# ESP32.net
KiCad netlist of a schematic drawn in Altium Designer
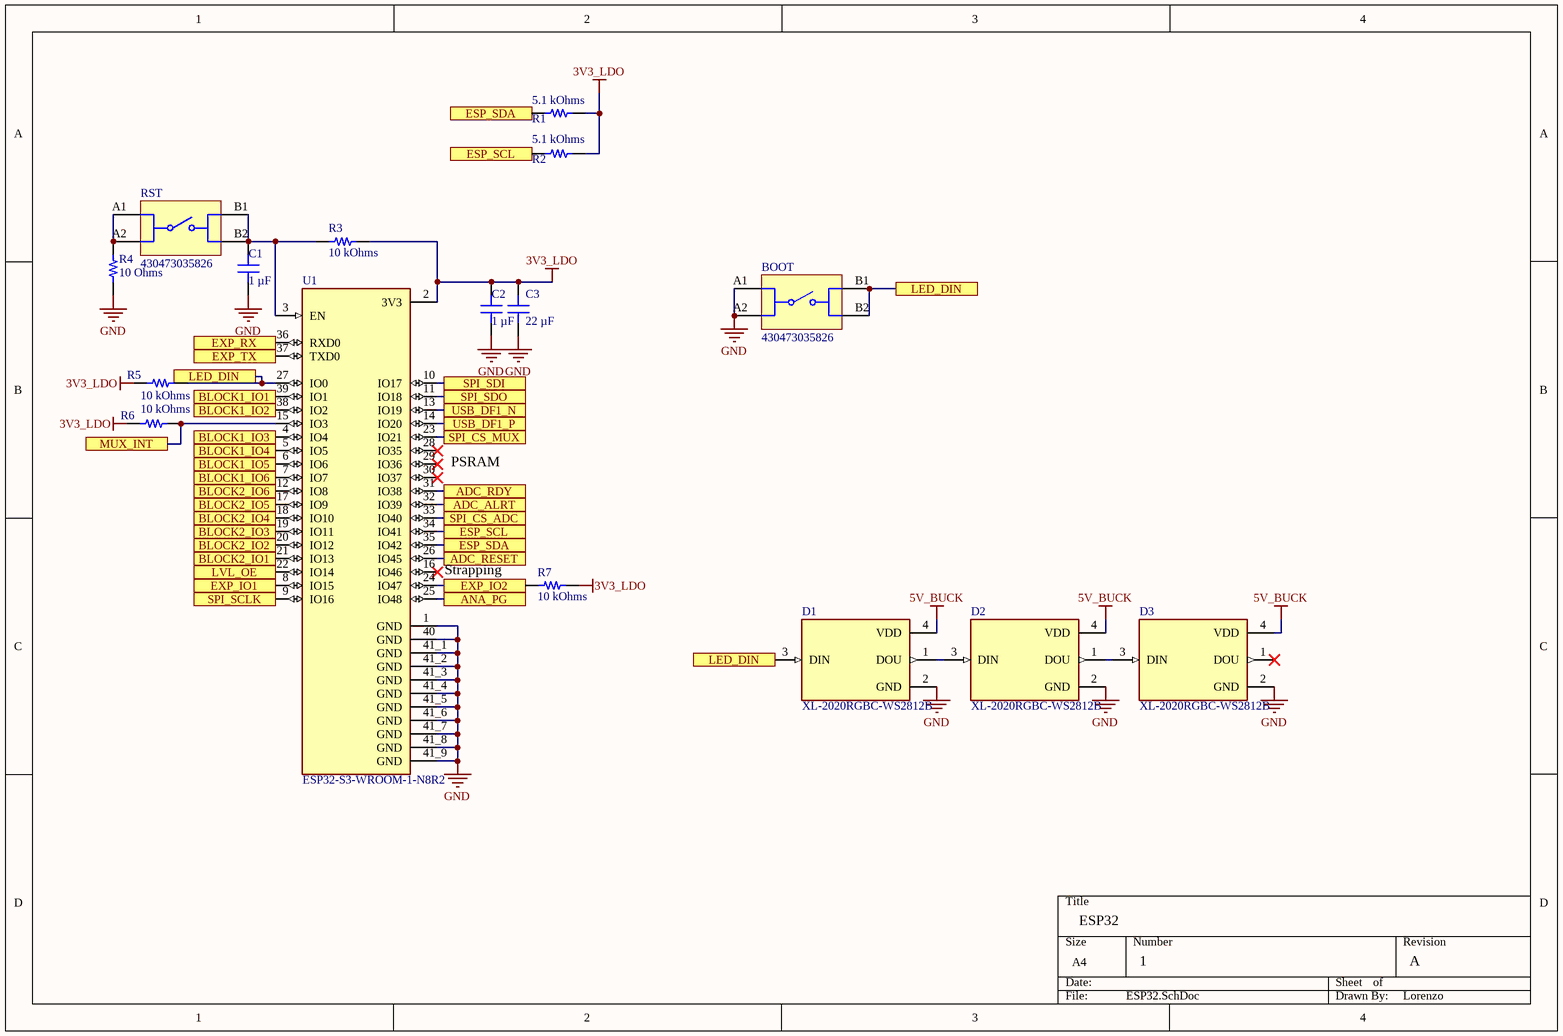
[diagram p0: ESP32.SchDoc]

(export (version "E")
  (design (tool "Eeschema 10.0.6"))
  (components
    (comp (ref "BOOT")
      (value "430473035826")
      (footprint "430473035826")
      (description "Switch Tactile Spst-no 0.05A 12V")
      (libsource (lib "Altium Content Vault") (part "SPST-NO_4P"))
    )
    (comp (ref "C1")
      (value "1 µF")
      (footprint "CAP 0603_1608")
      (description "CAP CER 1UF 50V X5R 0603")
      (fields
        (field (name "PART NUMBER") "C1608X5R1H105K080AB")
        (field (name "MANUFACTURER") "TDK Corporation")
      )
      (libsource (lib "Altium Database Library V2 Local") (part "Capacitor"))
    )
    (comp (ref "C2")
      (value "1 µF")
      (footprint "CAP 0603_1608")
      (description "CAP CER 1UF 50V X5R 0603")
      (fields
        (field (name "PART NUMBER") "C1608X5R1H105K080AB")
        (field (name "MANUFACTURER") "TDK Corporation")
      )
      (libsource (lib "Altium Database Library V2 Local") (part "Capacitor"))
    )
    (comp (ref "C3")
      (value "22 µF")
      (footprint "CAP 0603_1608")
      (description "CAP CER 22UF 6.3V X6S 0603")
      (fields (field (name "PART NUMBER") "CC0603MRX6S5BB226") (field (name "MANUFACTURER") "Yageo"))
      (libsource (lib "Altium Database Library V2 Local") (part "Capacitor"))
    )
    (comp (ref "D1")
      (value "XL-2020RGBC-WS2812B")
      (footprint "LED_XL-2020RGBC-WS2812B")
      (description "2020 RGB LED(BUILT-IN IC)")
      (fields (field (name "MF") "XINGLIGHT"))
      (libsource (lib "Lib") (part "XL-2020RGBC-WS2812B"))
    )
    (comp (ref "D2")
      (value "XL-2020RGBC-WS2812B")
      (footprint "LED_XL-2020RGBC-WS2812B")
      (description "2020 RGB LED(BUILT-IN IC)")
      (fields (field (name "MF") "XINGLIGHT"))
      (libsource (lib "Lib") (part "XL-2020RGBC-WS2812B"))
    )
    (comp (ref "D3")
      (value "XL-2020RGBC-WS2812B")
      (footprint "LED_XL-2020RGBC-WS2812B")
      (description "2020 RGB LED(BUILT-IN IC)")
      (fields (field (name "MF") "XINGLIGHT"))
      (libsource (lib "Lib") (part "XL-2020RGBC-WS2812B"))
    )
    (comp (ref "R1")
      (value "5.1 kOhms")
      (footprint "RES 0603_1608")
      (description "RES 5.1K OHM 1% 1/10W 0603")
      (fields
        (field (name "PART NUMBER") "RMCF0603FT5K10")
        (field (name "MANUFACTURER") "Stackpole Electronics Inc")
      )
      (libsource (lib "Altium Database Library V2 Local") (part "Resistor"))
    )
    (comp (ref "R2")
      (value "5.1 kOhms")
      (footprint "RES 0603_1608")
      (description "RES 5.1K OHM 1% 1/10W 0603")
      (fields
        (field (name "PART NUMBER") "RMCF0603FT5K10")
        (field (name "MANUFACTURER") "Stackpole Electronics Inc")
      )
      (libsource (lib "Altium Database Library V2 Local") (part "Resistor"))
    )
    (comp (ref "R3")
      (value "10 kOhms")
      (footprint "RES 0603_1608")
      (description "RES 10K OHM 1% 1/5W 0603")
      (fields
        (field (name "PART NUMBER") "SG73S1JTTD1002F")
        (field (name "MANUFACTURER") "KOA Speer Electronics, Inc.")
      )
      (libsource (lib "Altium Database Library V2 Local") (part "Resistor"))
    )
    (comp (ref "R4")
      (value "10 Ohms")
      (footprint "RES 0603_1608")
      (description "RES SMD 10 OHM 1% 1/4W 0603")
      (fields (field (name "PART NUMBER") "ESR03EZPF10R0") (field (name "MANUFACTURER") "Rohm Semiconductor"))
      (libsource (lib "Altium Database Library V2 Local") (part "Resistor"))
    )
    (comp (ref "R5")
      (value "10 kOhms")
      (footprint "RES 0603_1608")
      (description "RES 10K OHM 1% 1/5W 0603")
      (fields
        (field (name "PART NUMBER") "SG73S1JTTD1002F")
        (field (name "MANUFACTURER") "KOA Speer Electronics, Inc.")
      )
      (libsource (lib "Altium Database Library V2 Local") (part "Resistor"))
    )
    (comp (ref "R6")
      (value "10 kOhms")
      (footprint "RES 0603_1608")
      (description "RES 10K OHM 1% 1/5W 0603")
      (fields
        (field (name "PART NUMBER") "SG73S1JTTD1002F")
        (field (name "MANUFACTURER") "KOA Speer Electronics, Inc.")
      )
      (libsource (lib "Altium Database Library V2 Local") (part "Resistor"))
    )
    (comp (ref "R7")
      (value "10 kOhms")
      (footprint "RES 0603_1608")
      (description "RES 10K OHM 1% 1/5W 0603")
      (fields
        (field (name "PART NUMBER") "SG73S1JTTD1002F")
        (field (name "MANUFACTURER") "KOA Speer Electronics, Inc.")
      )
      (libsource (lib "Altium Database Library V2 Local") (part "Resistor"))
    )
    (comp (ref "RST")
      (value "430473035826")
      (footprint "430473035826")
      (description "Switch Tactile Spst-no 0.05A 12V")
      (libsource (lib "Altium Content Vault") (part "SPST-NO_4P"))
    )
    (comp (ref "U1")
      (value "ESP32-S3-WROOM-1-N8R2")
      (footprint "XCVR_ESP32-S3-WROOM-1-N8R2")
      (description "WiFi 802.11a/b/g/n, Bluetooth v5.0 Transceiver Module 2.4GHz Antenna Not Included -")
      (fields (field (name "MF") "Espressif Systems"))
      (libsource (lib "Lib") (part "ESP32-S3-WROOM-1-N8R2"))
    )
  )
  (nets
    (net (code "1") (name "/ADC_ALRT") (class "Default")
      (node (ref "U1") (pin "32") (pinfunction "IO39_32") (pintype "bidirectional"))
    )
    (net (code "2") (name "/ADC_RDY") (class "Default")
      (node (ref "U1") (pin "31") (pinfunction "IO38_31") (pintype "bidirectional"))
    )
    (net (code "3") (name "/ADC_RESET") (class "Default")
      (node (ref "U1") (pin "26") (pinfunction "IO45_26") (pintype "bidirectional"))
    )
    (net (code "4") (name "/ANA_PG") (class "Default")
      (node (ref "U1") (pin "25") (pinfunction "IO48_25") (pintype "bidirectional"))
    )
    (net (code "5") (name "/BLOCK1_IO1") (class "Default")
      (node (ref "U1") (pin "39") (pinfunction "IO1_39") (pintype "bidirectional"))
    )
    (net (code "6") (name "/BLOCK1_IO2") (class "Default")
      (node (ref "U1") (pin "38") (pinfunction "IO2_38") (pintype "bidirectional"))
    )
    (net (code "7") (name "/BLOCK1_IO3") (class "Default")
      (node (ref "U1") (pin "4") (pinfunction "IO4_4") (pintype "bidirectional"))
    )
    (net (code "8") (name "/BLOCK1_IO4") (class "Default")
      (node (ref "U1") (pin "5") (pinfunction "IO5_5") (pintype "bidirectional"))
    )
    (net (code "9") (name "/BLOCK1_IO5") (class "Default")
      (node (ref "U1") (pin "6") (pinfunction "IO6_6") (pintype "bidirectional"))
    )
    (net (code "10") (name "/BLOCK1_IO6") (class "Default")
      (node (ref "U1") (pin "7") (pinfunction "IO7_7") (pintype "bidirectional"))
    )
    (net (code "11") (name "/BLOCK2_IO1") (class "Default")
      (node (ref "U1") (pin "21") (pinfunction "IO13_21") (pintype "bidirectional"))
    )
    (net (code "12") (name "/BLOCK2_IO2") (class "Default")
      (node (ref "U1") (pin "20") (pinfunction "IO12_20") (pintype "bidirectional"))
    )
    (net (code "13") (name "/BLOCK2_IO3") (class "Default")
      (node (ref "U1") (pin "19") (pinfunction "IO11_19") (pintype "bidirectional"))
    )
    (net (code "14") (name "/BLOCK2_IO4") (class "Default")
      (node (ref "U1") (pin "18") (pinfunction "IO10_18") (pintype "bidirectional"))
    )
    (net (code "15") (name "/BLOCK2_IO5") (class "Default")
      (node (ref "U1") (pin "17") (pinfunction "IO9_17") (pintype "bidirectional"))
    )
    (net (code "16") (name "/BLOCK2_IO6") (class "Default")
      (node (ref "U1") (pin "12") (pinfunction "IO8_12") (pintype "bidirectional"))
    )
    (net (code "17") (name "/ESP_SCL") (class "Default")
      (node (ref "R2") (pin "1") (pinfunction "1_1") (pintype "passive"))
      (node (ref "U1") (pin "34") (pinfunction "IO41_34") (pintype "bidirectional"))
    )
    (net (code "18") (name "/ESP_SDA") (class "Default")
      (node (ref "R1") (pin "1") (pinfunction "1_1") (pintype "passive"))
      (node (ref "U1") (pin "35") (pinfunction "IO42_35") (pintype "bidirectional"))
    )
    (net (code "19") (name "/EXP_IO1") (class "Default")
      (node (ref "U1") (pin "8") (pinfunction "IO15_8") (pintype "bidirectional"))
    )
    (net (code "20") (name "/EXP_IO2") (class "Default")
      (node (ref "R7") (pin "2") (pinfunction "2_2") (pintype "passive"))
      (node (ref "U1") (pin "24") (pinfunction "IO47_24") (pintype "bidirectional"))
    )
    (net (code "21") (name "/EXP_RX") (class "Default")
      (node (ref "U1") (pin "36") (pinfunction "RXD0_36") (pintype "bidirectional"))
    )
    (net (code "22") (name "/EXP_TX") (class "Default")
      (node (ref "U1") (pin "37") (pinfunction "TXD0_37") (pintype "bidirectional"))
    )
    (net (code "23") (name "/LED_DIN") (class "Default")
      (node (ref "BOOT") (pin "B1") (pinfunction "B1_B1") (pintype "passive"))
      (node (ref "BOOT") (pin "B2") (pinfunction "B2_B2") (pintype "passive"))
      (node (ref "D1") (pin "3") (pinfunction "DIN_3") (pintype "input"))
      (node (ref "R5") (pin "2") (pinfunction "2_2") (pintype "passive"))
      (node (ref "U1") (pin "27") (pinfunction "IO0_27") (pintype "bidirectional"))
    )
    (net (code "24") (name "/LVL_OE") (class "Default")
      (node (ref "U1") (pin "22") (pinfunction "IO14_22") (pintype "bidirectional"))
    )
    (net (code "25") (name "/MUX_INT") (class "Default")
      (node (ref "R6") (pin "2") (pinfunction "2_2") (pintype "passive"))
      (node (ref "U1") (pin "15") (pinfunction "IO3_15") (pintype "bidirectional"))
    )
    (net (code "26") (name "/SPI_CS_ADC") (class "Default")
      (node (ref "U1") (pin "33") (pinfunction "IO40_33") (pintype "bidirectional"))
    )
    (net (code "27") (name "/SPI_CS_MUX") (class "Default")
      (node (ref "U1") (pin "23") (pinfunction "IO21_23") (pintype "bidirectional"))
    )
    (net (code "28") (name "/SPI_SCLK") (class "Default")
      (node (ref "U1") (pin "9") (pinfunction "IO16_9") (pintype "bidirectional"))
    )
    (net (code "29") (name "/SPI_SDI") (class "Default")
      (node (ref "U1") (pin "10") (pinfunction "IO17_10") (pintype "bidirectional"))
    )
    (net (code "30") (name "/SPI_SDO") (class "Default")
      (node (ref "U1") (pin "11") (pinfunction "IO18_11") (pintype "bidirectional"))
    )
    (net (code "31") (name "/USB_DF1_N") (class "Default")
      (node (ref "U1") (pin "13") (pinfunction "IO19_13") (pintype "bidirectional"))
    )
    (net (code "32") (name "/USB_DF1_P") (class "Default")
      (node (ref "U1") (pin "14") (pinfunction "IO20_14") (pintype "bidirectional"))
    )
    (net (code "33") (name "3V3_LDO") (class "Default")
      (node (ref "C2") (pin "2") (pinfunction "2_2") (pintype "passive"))
      (node (ref "C3") (pin "2") (pinfunction "2_2") (pintype "passive"))
      (node (ref "R1") (pin "2") (pinfunction "2_2") (pintype "passive"))
      (node (ref "R2") (pin "2") (pinfunction "2_2") (pintype "passive"))
      (node (ref "R3") (pin "2") (pinfunction "2_2") (pintype "passive"))
      (node (ref "R5") (pin "1") (pinfunction "1_1") (pintype "passive"))
      (node (ref "R6") (pin "1") (pinfunction "1_1") (pintype "passive"))
      (node (ref "R7") (pin "1") (pinfunction "1_1") (pintype "passive"))
      (node (ref "U1") (pin "2") (pinfunction "3V3_2") (pintype "power_in"))
    )
    (net (code "34") (name "5V_BUCK") (class "Default")
      (node (ref "D1") (pin "4") (pinfunction "VDD_4") (pintype "power_in"))
      (node (ref "D2") (pin "4") (pinfunction "VDD_4") (pintype "power_in"))
      (node (ref "D3") (pin "4") (pinfunction "VDD_4") (pintype "power_in"))
    )
    (net (code "35") (name "GND") (class "Default")
      (node (ref "BOOT") (pin "A1") (pinfunction "A1_A1") (pintype "passive"))
      (node (ref "BOOT") (pin "A2") (pinfunction "A2_A2") (pintype "passive"))
      (node (ref "C1") (pin "1") (pinfunction "1_1") (pintype "passive"))
      (node (ref "C2") (pin "1") (pinfunction "1_1") (pintype "passive"))
      (node (ref "C3") (pin "1") (pinfunction "1_1") (pintype "passive"))
      (node (ref "D1") (pin "2") (pinfunction "GND_2") (pintype "power_in"))
      (node (ref "D2") (pin "2") (pinfunction "GND_2") (pintype "power_in"))
      (node (ref "D3") (pin "2") (pinfunction "GND_2") (pintype "power_in"))
      (node (ref "R4") (pin "1") (pinfunction "1_1") (pintype "passive"))
      (node (ref "U1") (pin "1") (pinfunction "GND_1") (pintype "power_in"))
      (node (ref "U1") (pin "40") (pinfunction "GND_40") (pintype "power_in"))
      (node (ref "U1") (pin "41_1") (pinfunction "GND_41_1") (pintype "power_in"))
      (node (ref "U1") (pin "41_2") (pinfunction "GND_41_2") (pintype "power_in"))
      (node (ref "U1") (pin "41_3") (pinfunction "GND_41_3") (pintype "power_in"))
      (node (ref "U1") (pin "41_4") (pinfunction "GND_41_4") (pintype "power_in"))
      (node (ref "U1") (pin "41_5") (pinfunction "GND_41_5") (pintype "power_in"))
      (node (ref "U1") (pin "41_6") (pinfunction "GND_41_6") (pintype "power_in"))
      (node (ref "U1") (pin "41_7") (pinfunction "GND_41_7") (pintype "power_in"))
      (node (ref "U1") (pin "41_8") (pinfunction "GND_41_8") (pintype "power_in"))
      (node (ref "U1") (pin "41_9") (pinfunction "GND_41_9") (pintype "power_in"))
    )
    (net (code "36") (name "Net-(D1-DOU)") (class "Default")
      (node (ref "D1") (pin "1") (pinfunction "DOU_1") (pintype "output"))
      (node (ref "D2") (pin "3") (pinfunction "DIN_3") (pintype "input"))
    )
    (net (code "37") (name "Net-(D2-DOU)") (class "Default")
      (node (ref "D2") (pin "1") (pinfunction "DOU_1") (pintype "output"))
      (node (ref "D3") (pin "3") (pinfunction "DIN_3") (pintype "input"))
    )
    (net (code "38") (name "Net-(R4-Pad2)") (class "Default")
      (node (ref "R4") (pin "2") (pinfunction "2_2") (pintype "passive"))
      (node (ref "RST") (pin "A1") (pinfunction "A1_A1") (pintype "passive"))
      (node (ref "RST") (pin "A2") (pinfunction "A2_A2") (pintype "passive"))
    )
    (net (code "39") (name "Net-(U1-EN)") (class "Default")
      (node (ref "C1") (pin "2") (pinfunction "2_2") (pintype "passive"))
      (node (ref "R3") (pin "1") (pinfunction "1_1") (pintype "passive"))
      (node (ref "RST") (pin "B1") (pinfunction "B1_B1") (pintype "passive"))
      (node (ref "RST") (pin "B2") (pinfunction "B2_B2") (pintype "passive"))
      (node (ref "U1") (pin "3") (pinfunction "EN_3") (pintype "input"))
    )
    (net (code "40") (name "unconnected-(D3-DOU-Pad1)") (class "Default")
      (node (ref "D3") (pin "1") (pinfunction "DOU_1") (pintype "output+no_connect"))
    )
    (net (code "41") (name "unconnected-(U1-IO35-Pad28)") (class "Default")
      (node (ref "U1") (pin "28") (pinfunction "IO35_28") (pintype "bidirectional+no_connect"))
    )
    (net (code "42") (name "unconnected-(U1-IO36-Pad29)") (class "Default")
      (node (ref "U1") (pin "29") (pinfunction "IO36_29") (pintype "bidirectional+no_connect"))
    )
    (net (code "43") (name "unconnected-(U1-IO37-Pad30)") (class "Default")
      (node (ref "U1") (pin "30") (pinfunction "IO37_30") (pintype "bidirectional+no_connect"))
    )
    (net (code "44") (name "unconnected-(U1-IO46-Pad16)") (class "Default")
      (node (ref "U1") (pin "16") (pinfunction "IO46_16") (pintype "bidirectional+no_connect"))
    )
  )
)
